# rgbpong.net
KiCad netlist of a schematic drawn in EAGLE
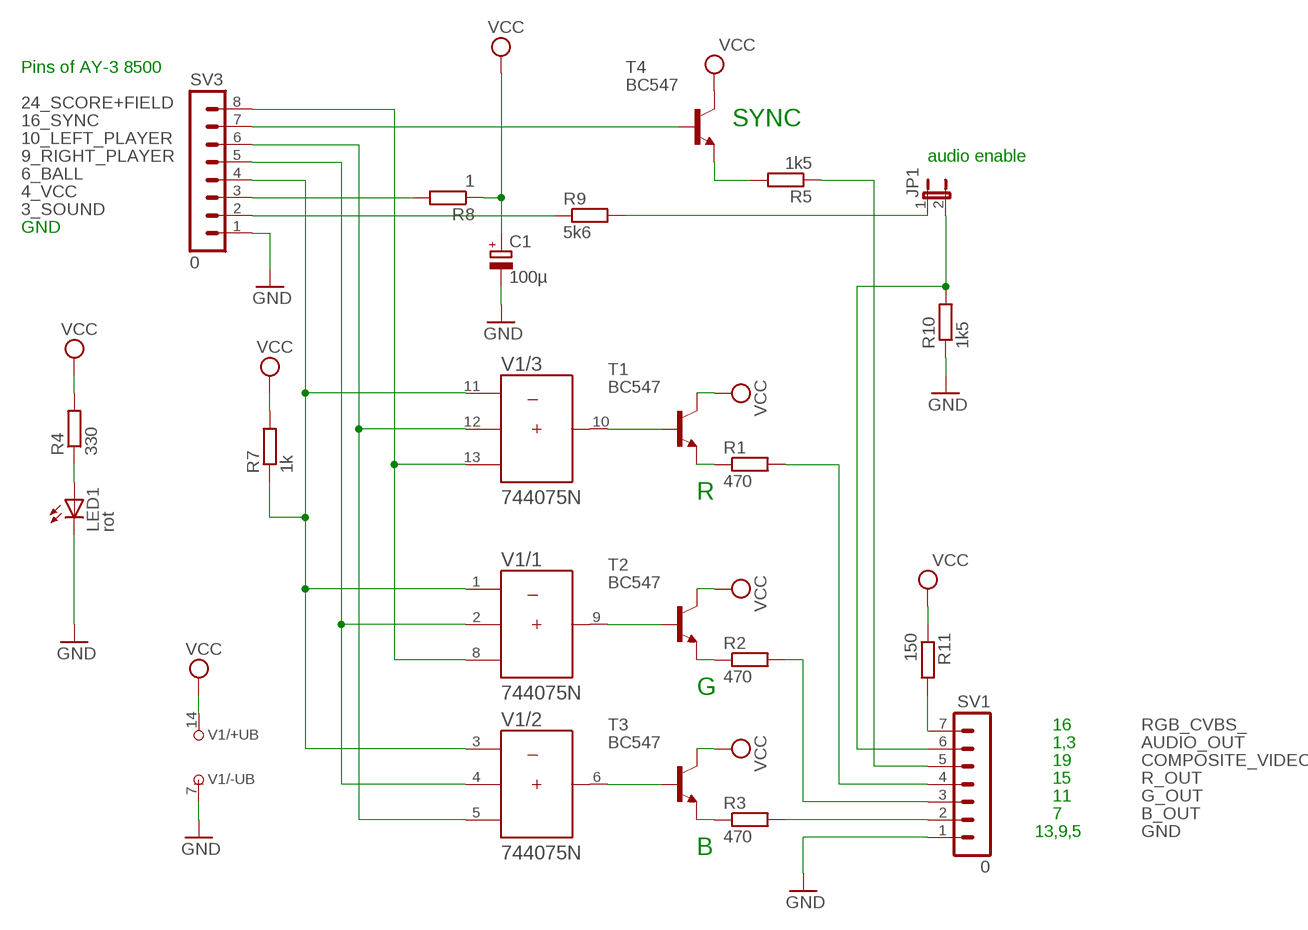
[diagram p0: schematic, sheet 1]

(export (version "E")
  (design (tool "Eeschema 10.0.6"))
  (components
    (comp (ref "C1")
      (value "100µ")
      (footprint "eagle-import:E2,5-5")
      (libsource (lib "eagle-import") (part "CPOL-EUE2.5-5"))
    )
    (comp (ref "JP1")
      (value "0")
      (footprint "eagle-import:JP1")
      (libsource (lib "eagle-import") (part "JP1E"))
    )
    (comp (ref "LED1")
      (value "rot")
      (footprint "eagle-import:LED3MM")
      (libsource (lib "eagle-import") (part "LED3MM"))
    )
    (comp (ref "R1")
      (value "470")
      (footprint "eagle-import:0207_10")
      (libsource (lib "eagle-import") (part "R-EU_0207/10"))
    )
    (comp (ref "R2")
      (value "470")
      (footprint "eagle-import:0207_10")
      (libsource (lib "eagle-import") (part "R-EU_0207/10"))
    )
    (comp (ref "R3")
      (value "470")
      (footprint "eagle-import:0207_10")
      (libsource (lib "eagle-import") (part "R-EU_0207/10"))
    )
    (comp (ref "R4")
      (value "330")
      (footprint "eagle-import:0207_10")
      (libsource (lib "eagle-import") (part "R-EU_0207/10"))
    )
    (comp (ref "R5")
      (value "1k5")
      (footprint "eagle-import:0207_10")
      (libsource (lib "eagle-import") (part "R-EU_0207/10"))
    )
    (comp (ref "R7")
      (value "1k")
      (footprint "eagle-import:0207_15")
      (libsource (lib "eagle-import") (part "R-EU_0207/15"))
    )
    (comp (ref "R8")
      (value "1")
      (footprint "eagle-import:0207_15")
      (libsource (lib "eagle-import") (part "R-EU_0207/15"))
    )
    (comp (ref "R9")
      (value "5k6")
      (footprint "eagle-import:0207_10")
      (libsource (lib "eagle-import") (part "R-EU_0207/10"))
    )
    (comp (ref "R10")
      (value "1k5")
      (footprint "eagle-import:0207_10")
      (libsource (lib "eagle-import") (part "R-EU_0207/10"))
    )
    (comp (ref "R11")
      (value "150")
      (footprint "eagle-import:0207_10")
      (libsource (lib "eagle-import") (part "R-EU_0207/10"))
    )
    (comp (ref "SV1")
      (value "0")
      (footprint "eagle-import:MA07-1")
      (libsource (lib "eagle-import") (part "MA07-1"))
    )
    (comp (ref "SV3")
      (value "0")
      (footprint "eagle-import:MA08-1")
      (libsource (lib "eagle-import") (part "MA08-1"))
    )
    (comp (ref "T1")
      (value "BC547")
      (footprint "eagle-import:TO92-ECB")
      (libsource (lib "eagle-import") (part "-NPN-TO92-ECB"))
    )
    (comp (ref "T2")
      (value "BC547")
      (footprint "eagle-import:TO92-ECB")
      (libsource (lib "eagle-import") (part "-NPN-TO92-ECB"))
    )
    (comp (ref "T3")
      (value "BC547")
      (footprint "eagle-import:TO92-ECB")
      (libsource (lib "eagle-import") (part "-NPN-TO92-ECB"))
    )
    (comp (ref "T4")
      (value "BC547")
      (footprint "eagle-import:TO92-ECB")
      (libsource (lib "eagle-import") (part "-NPN-TO92-ECB"))
    )
    (comp (ref "V1")
      (value "744075N")
      (footprint "eagle-import:DIL14")
      (libsource (lib "eagle-import") (part "744075N"))
    )
  )
  (nets
    (net (code "1") (name "/3_SOUND") (class "Default")
      (node (ref "R9") (pin "1") (pinfunction "1_1") (pintype "passive"))
      (node (ref "SV3") (pin "2") (pinfunction "2_2") (pintype "passive"))
    )
    (net (code "2") (name "/4_VCC") (class "Default")
      (node (ref "R8") (pin "2") (pinfunction "2_2") (pintype "passive"))
      (node (ref "SV3") (pin "3") (pinfunction "3_3") (pintype "passive"))
    )
    (net (code "3") (name "/6_BALL") (class "Default")
      (node (ref "R7") (pin "1") (pinfunction "1_1") (pintype "passive"))
      (node (ref "SV3") (pin "4") (pinfunction "4_4") (pintype "passive"))
      (node (ref "V1") (pin "1") (pinfunction "A_1") (pintype "input"))
      (node (ref "V1") (pin "11") (pinfunction "A_11") (pintype "input"))
      (node (ref "V1") (pin "3") (pinfunction "A_3") (pintype "input"))
    )
    (net (code "4") (name "/9_RIGHT_PLAYER") (class "Default")
      (node (ref "SV3") (pin "5") (pinfunction "5_5") (pintype "passive"))
      (node (ref "V1") (pin "2") (pinfunction "B_2") (pintype "input"))
      (node (ref "V1") (pin "4") (pinfunction "B_4") (pintype "input"))
    )
    (net (code "5") (name "/10_LEFT_PLAYER") (class "Default")
      (node (ref "SV3") (pin "6") (pinfunction "6_6") (pintype "passive"))
      (node (ref "V1") (pin "12") (pinfunction "B_12") (pintype "input"))
      (node (ref "V1") (pin "5") (pinfunction "C_5") (pintype "input"))
    )
    (net (code "6") (name "/16_SYNC") (class "Default")
      (node (ref "SV3") (pin "7") (pinfunction "7_7") (pintype "passive"))
      (node (ref "T4") (pin "B") (pinfunction "B_B") (pintype "passive"))
    )
    (net (code "7") (name "/24_SCORE+FIELD") (class "Default")
      (node (ref "SV3") (pin "8") (pinfunction "8_8") (pintype "passive"))
      (node (ref "V1") (pin "13") (pinfunction "C_13") (pintype "input"))
      (node (ref "V1") (pin "8") (pinfunction "C_8") (pintype "input"))
    )
    (net (code "8") (name "/AUDIO_OUT") (class "Default")
      (node (ref "JP1") (pin "2") (pinfunction "2_2") (pintype "passive"))
      (node (ref "R10") (pin "2") (pinfunction "2_2") (pintype "passive"))
      (node (ref "SV1") (pin "6") (pinfunction "6_6") (pintype "passive"))
    )
    (net (code "9") (name "/B_OUT") (class "Default")
      (node (ref "R3") (pin "2") (pinfunction "2_2") (pintype "passive"))
      (node (ref "SV1") (pin "2") (pinfunction "2_2") (pintype "passive"))
    )
    (net (code "10") (name "/COMPOSITE_VIDEO") (class "Default")
      (node (ref "R5") (pin "1") (pinfunction "1_1") (pintype "passive"))
      (node (ref "SV1") (pin "5") (pinfunction "5_5") (pintype "passive"))
    )
    (net (code "11") (name "/G_OUT") (class "Default")
      (node (ref "R2") (pin "2") (pinfunction "2_2") (pintype "passive"))
      (node (ref "SV1") (pin "3") (pinfunction "3_3") (pintype "passive"))
    )
    (net (code "12") (name "/RGB_CVBS_") (class "Default")
      (node (ref "R11") (pin "2") (pinfunction "2_2") (pintype "passive"))
      (node (ref "SV1") (pin "7") (pinfunction "7_7") (pintype "passive"))
    )
    (net (code "13") (name "/R_OUT") (class "Default")
      (node (ref "R1") (pin "2") (pinfunction "2_2") (pintype "passive"))
      (node (ref "SV1") (pin "4") (pinfunction "4_4") (pintype "passive"))
    )
    (net (code "14") (name "GND") (class "Default")
      (node (ref "C1") (pin "-") (pinfunction "-_-") (pintype "passive"))
      (node (ref "LED1") (pin "K") (pinfunction "C_K") (pintype "passive"))
      (node (ref "R10") (pin "1") (pinfunction "1_1") (pintype "passive"))
      (node (ref "SV1") (pin "1") (pinfunction "1_1") (pintype "passive"))
      (node (ref "SV3") (pin "1") (pinfunction "1_1") (pintype "passive"))
      (node (ref "V1") (pin "7") (pinfunction "-UB_7") (pintype "power_in"))
    )
    (net (code "15") (name "Net-(JP1-Pad1)") (class "Default")
      (node (ref "JP1") (pin "1") (pinfunction "1_1") (pintype "passive"))
      (node (ref "R9") (pin "2") (pinfunction "2_2") (pintype "passive"))
    )
    (net (code "16") (name "Net-(LED1-PadA)") (class "Default")
      (node (ref "LED1") (pin "A") (pinfunction "A_A") (pintype "passive"))
      (node (ref "R4") (pin "1") (pinfunction "1_1") (pintype "passive"))
    )
    (net (code "17") (name "Net-(R1-Pad1)") (class "Default")
      (node (ref "R1") (pin "1") (pinfunction "1_1") (pintype "passive"))
      (node (ref "T1") (pin "E") (pinfunction "E_E") (pintype "passive"))
    )
    (net (code "18") (name "Net-(R2-Pad1)") (class "Default")
      (node (ref "R2") (pin "1") (pinfunction "1_1") (pintype "passive"))
      (node (ref "T2") (pin "E") (pinfunction "E_E") (pintype "passive"))
    )
    (net (code "19") (name "Net-(R3-Pad1)") (class "Default")
      (node (ref "R3") (pin "1") (pinfunction "1_1") (pintype "passive"))
      (node (ref "T3") (pin "E") (pinfunction "E_E") (pintype "passive"))
    )
    (net (code "20") (name "Net-(R5-Pad2)") (class "Default")
      (node (ref "R5") (pin "2") (pinfunction "2_2") (pintype "passive"))
      (node (ref "T4") (pin "E") (pinfunction "E_E") (pintype "passive"))
    )
    (net (code "21") (name "Net-(V1C-Y)") (class "Default")
      (node (ref "T2") (pin "B") (pinfunction "B_B") (pintype "passive"))
      (node (ref "V1") (pin "9") (pinfunction "Y_9") (pintype "output"))
    )
    (net (code "22") (name "Net-(V1D-Y)") (class "Default")
      (node (ref "T3") (pin "B") (pinfunction "B_B") (pintype "passive"))
      (node (ref "V1") (pin "6") (pinfunction "Y_6") (pintype "output"))
    )
    (net (code "23") (name "Net-(V1E-Y)") (class "Default")
      (node (ref "T1") (pin "B") (pinfunction "B_B") (pintype "passive"))
      (node (ref "V1") (pin "10") (pinfunction "Y_10") (pintype "output"))
    )
    (net (code "24") (name "VCC") (class "Default")
      (node (ref "C1") (pin "+") (pinfunction "+_+") (pintype "passive"))
      (node (ref "R11") (pin "1") (pinfunction "1_1") (pintype "passive"))
      (node (ref "R4") (pin "2") (pinfunction "2_2") (pintype "passive"))
      (node (ref "R7") (pin "2") (pinfunction "2_2") (pintype "passive"))
      (node (ref "R8") (pin "1") (pinfunction "1_1") (pintype "passive"))
      (node (ref "T1") (pin "C") (pinfunction "C_C") (pintype "passive"))
      (node (ref "T2") (pin "C") (pinfunction "C_C") (pintype "passive"))
      (node (ref "T3") (pin "C") (pinfunction "C_C") (pintype "passive"))
      (node (ref "T4") (pin "C") (pinfunction "C_C") (pintype "passive"))
      (node (ref "V1") (pin "14") (pinfunction "+UB_14") (pintype "power_in"))
    )
  )
)
